# square_Rev1.net
KiCad netlist of a schematic drawn in EAGLE
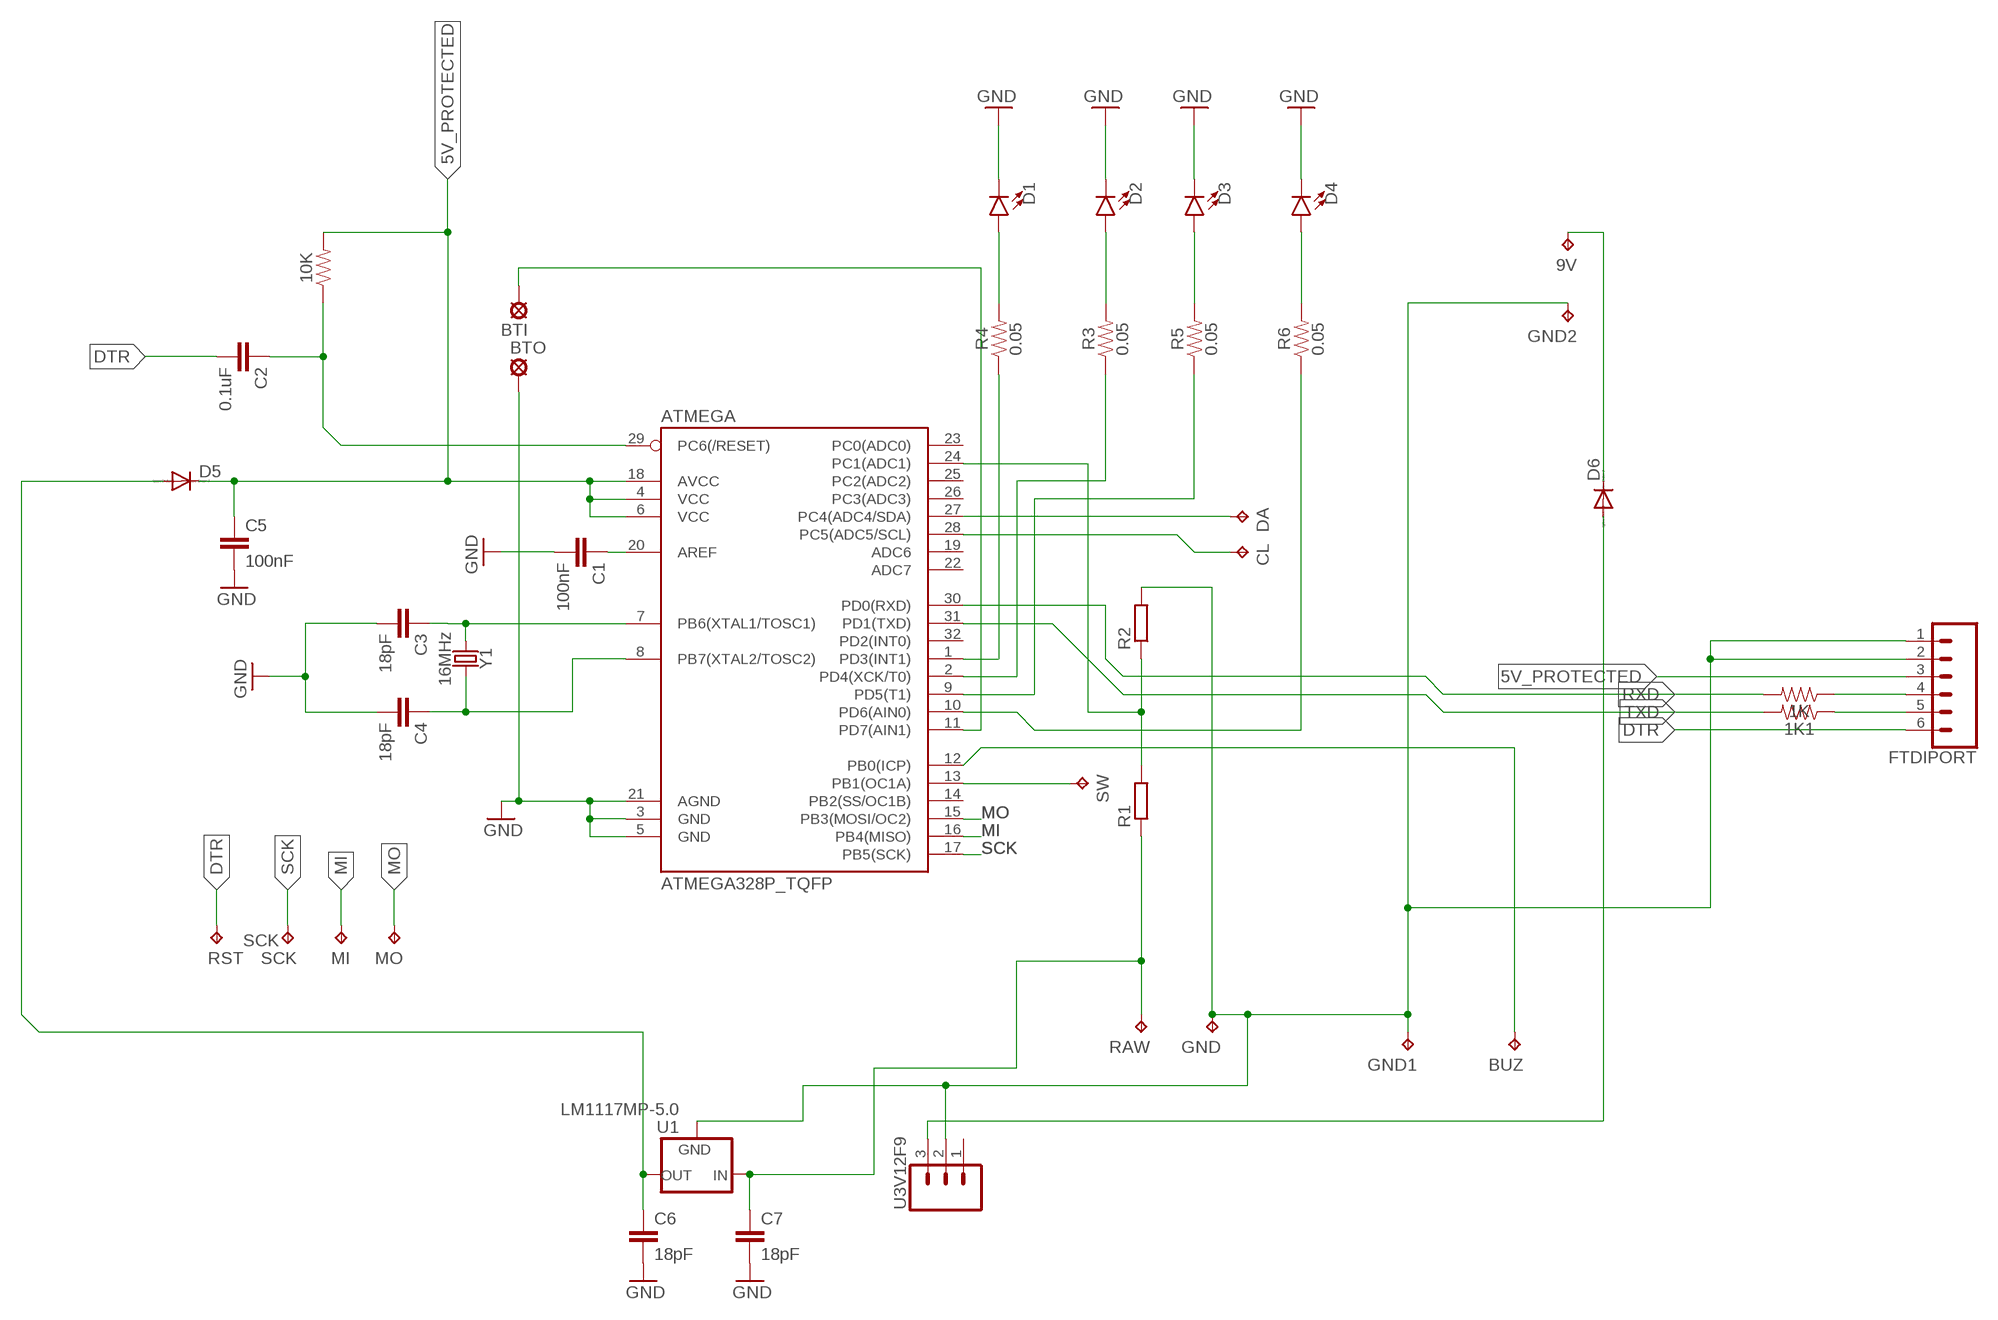
[diagram p0: schematic, sheet 1]

(export (version "E")
  (design (tool "Eeschema 10.0.6"))
  (components
    (comp (ref "1K")
      (value "0.27OHM-0603-1/10W-1%")
      (footprint "eagle-import:0603")
      (libsource (lib "eagle-import") (part "0.27OHM-0603-1/10W-1%"))
    )
    (comp (ref "1K1")
      (value "0.27OHM-0603-1/10W-1%")
      (footprint "eagle-import:0603")
      (libsource (lib "eagle-import") (part "0.27OHM-0603-1/10W-1%"))
    )
    (comp (ref "9V")
      (value "TPB2,54")
      (footprint "eagle-import:B2,54")
      (libsource (lib "eagle-import") (part "TPB2,54"))
    )
    (comp (ref "10K")
      (value "0.27OHM-0603-1/10W-1%")
      (footprint "eagle-import:0603")
      (libsource (lib "eagle-import") (part "0.27OHM-0603-1/10W-1%"))
    )
    (comp (ref "ATMEGA")
      (value "ATMEGA328P_TQFP")
      (footprint "eagle-import:TQFP32-08")
      (libsource (lib "eagle-import") (part "ATMEGA328P_TQFP"))
    )
    (comp (ref "BTI")
      (value "LSP10")
      (footprint "eagle-import:LSP10")
      (libsource (lib "eagle-import") (part "LSP10"))
    )
    (comp (ref "BTO")
      (value "LSP10")
      (footprint "eagle-import:LSP10")
      (libsource (lib "eagle-import") (part "LSP10"))
    )
    (comp (ref "BUZ")
      (value "TPB2,54")
      (footprint "eagle-import:B2,54")
      (libsource (lib "eagle-import") (part "TPB2,54"))
    )
    (comp (ref "C1")
      (value "100nF")
      (footprint "eagle-import:0603")
      (libsource (lib "eagle-import") (part "10NF-0603-50V-10%"))
    )
    (comp (ref "C2")
      (value "0.1uF")
      (footprint "eagle-import:0603")
      (libsource (lib "eagle-import") (part "10NF-0603-50V-10%"))
    )
    (comp (ref "C3")
      (value "18pF")
      (footprint "eagle-import:0603")
      (libsource (lib "eagle-import") (part "10NF-0603-50V-10%"))
    )
    (comp (ref "C4")
      (value "18pF")
      (footprint "eagle-import:0603")
      (libsource (lib "eagle-import") (part "10NF-0603-50V-10%"))
    )
    (comp (ref "C5")
      (value "100nF")
      (footprint "eagle-import:0603")
      (libsource (lib "eagle-import") (part "10NF-0603-50V-10%"))
    )
    (comp (ref "C6")
      (value "18pF")
      (footprint "eagle-import:0603")
      (libsource (lib "eagle-import") (part "10NF-0603-50V-10%"))
    )
    (comp (ref "C7")
      (value "18pF")
      (footprint "eagle-import:0603")
      (libsource (lib "eagle-import") (part "10NF-0603-50V-10%"))
    )
    (comp (ref "CL")
      (value "TPB1,27")
      (footprint "eagle-import:B1,27")
      (libsource (lib "eagle-import") (part "TPB1,27"))
    )
    (comp (ref "D1")
      (value "LED1206")
      (footprint "eagle-import:LED-1206")
      (libsource (lib "eagle-import") (part "LED1206"))
    )
    (comp (ref "D2")
      (value "LED1206")
      (footprint "eagle-import:LED-1206")
      (libsource (lib "eagle-import") (part "LED1206"))
    )
    (comp (ref "D3")
      (value "LED1206")
      (footprint "eagle-import:LED-1206")
      (libsource (lib "eagle-import") (part "LED1206"))
    )
    (comp (ref "D4")
      (value "LED1206")
      (footprint "eagle-import:LED-1206")
      (libsource (lib "eagle-import") (part "LED1206"))
    )
    (comp (ref "D5")
      (value "DIODE-SOD106A-R")
      (footprint "eagle-import:SOD106A-R")
      (libsource (lib "eagle-import") (part "DIODE-SOD106A-R"))
    )
    (comp (ref "D6")
      (value "DIODE-SOD106A-R")
      (footprint "eagle-import:SOD106A-R")
      (libsource (lib "eagle-import") (part "DIODE-SOD106A-R"))
    )
    (comp (ref "DA")
      (value "TPB1,27")
      (footprint "eagle-import:B1,27")
      (libsource (lib "eagle-import") (part "TPB1,27"))
    )
    (comp (ref "FTDIPORT")
      (value "CONN_06SMD-1MM")
      (footprint "eagle-import:1X06-1MM")
      (libsource (lib "eagle-import") (part "CONN_06SMD-1MM"))
    )
    (comp (ref "GND")
      (value "TPB2,54")
      (footprint "eagle-import:B2,54")
      (libsource (lib "eagle-import") (part "TPB2,54"))
    )
    (comp (ref "GND1")
      (value "TPB2,54")
      (footprint "eagle-import:B2,54")
      (libsource (lib "eagle-import") (part "TPB2,54"))
    )
    (comp (ref "GND2")
      (value "TPB2,54")
      (footprint "eagle-import:B2,54")
      (libsource (lib "eagle-import") (part "TPB2,54"))
    )
    (comp (ref "MI")
      (value "TPB1,27")
      (footprint "eagle-import:B1,27")
      (libsource (lib "eagle-import") (part "TPB1,27"))
    )
    (comp (ref "MO")
      (value "TPB1,27")
      (footprint "eagle-import:B1,27")
      (libsource (lib "eagle-import") (part "TPB1,27"))
    )
    (comp (ref "R1")
      (value "R-EU_R1206")
      (footprint "eagle-import:R1206")
      (libsource (lib "eagle-import") (part "R-EU_R1206"))
    )
    (comp (ref "R2")
      (value "R-EU_R1206")
      (footprint "eagle-import:R1206")
      (libsource (lib "eagle-import") (part "R-EU_R1206"))
    )
    (comp (ref "R3")
      (value "0.05")
      (footprint "eagle-import:0603")
      (libsource (lib "eagle-import") (part "0.05OHM-0603-1/5W-1%"))
    )
    (comp (ref "R4")
      (value "0.05")
      (footprint "eagle-import:0603")
      (libsource (lib "eagle-import") (part "0.05OHM-0603-1/5W-1%"))
    )
    (comp (ref "R5")
      (value "0.05")
      (footprint "eagle-import:0603")
      (libsource (lib "eagle-import") (part "0.05OHM-0603-1/5W-1%"))
    )
    (comp (ref "R6")
      (value "0.05")
      (footprint "eagle-import:0603")
      (libsource (lib "eagle-import") (part "0.05OHM-0603-1/5W-1%"))
    )
    (comp (ref "RAW")
      (value "TPB2,54")
      (footprint "eagle-import:B2,54")
      (libsource (lib "eagle-import") (part "TPB2,54"))
    )
    (comp (ref "RST")
      (value "TPB1,27")
      (footprint "eagle-import:B1,27")
      (libsource (lib "eagle-import") (part "TPB1,27"))
    )
    (comp (ref "SCK")
      (value "TPB1,27")
      (footprint "eagle-import:B1,27")
      (fields (field (name "TP_SIGNAL_NAME") "SCK"))
      (libsource (lib "eagle-import") (part "TPB1,27"))
    )
    (comp (ref "SW")
      (value "TPB1,27")
      (footprint "eagle-import:B1,27")
      (libsource (lib "eagle-import") (part "TPB1,27"))
    )
    (comp (ref "U1")
      (value "LM1117MP-5.0")
      (footprint "eagle-import:SOT223")
      (fields (field (name "MF") "Texas Instruments"))
      (libsource (lib "eagle-import") (part "LM1117?-MP5.0"))
    )
    (comp (ref "U3V12F9")
      (value "CONN_03")
      (footprint "eagle-import:1X03")
      (libsource (lib "eagle-import") (part "CONN_03"))
    )
    (comp (ref "Y1")
      (value "16MHz")
      (footprint "eagle-import:CRYSTAL-SMD-5X3.2-2PAD")
      (libsource (lib "eagle-import") (part "CRYSTALSMD-5X3.2-2PAD"))
    )
  )
  (nets
    (net (code "1") (name "5V_PROTECTED") (class "Default")
      (node (ref "10K") (pin "2") (pinfunction "2_2") (pintype "passive"))
      (node (ref "ATMEGA") (pin "18") (pinfunction "AVCC_18") (pintype "bidirectional"))
      (node (ref "ATMEGA") (pin "4") (pinfunction "VCC_4") (pintype "bidirectional"))
      (node (ref "ATMEGA") (pin "6") (pinfunction "VCC_6") (pintype "bidirectional"))
      (node (ref "C5") (pin "1") (pinfunction "1_1") (pintype "passive"))
      (node (ref "D5") (pin "C") (pinfunction "C_C") (pintype "passive"))
      (node (ref "FTDIPORT") (pin "3") (pinfunction "3_3") (pintype "passive"))
    )
    (net (code "2") (name "DTR") (class "Default")
      (node (ref "C2") (pin "2") (pinfunction "2_2") (pintype "passive"))
      (node (ref "FTDIPORT") (pin "6") (pinfunction "6_6") (pintype "passive"))
      (node (ref "RST") (pin "TP") (pinfunction "TP_TP") (pintype "input"))
    )
    (net (code "3") (name "GND") (class "Default")
      (node (ref "ATMEGA") (pin "21") (pinfunction "AGND_21") (pintype "bidirectional"))
      (node (ref "ATMEGA") (pin "3") (pinfunction "GND_3") (pintype "bidirectional"))
      (node (ref "ATMEGA") (pin "5") (pinfunction "GND_5") (pintype "bidirectional"))
      (node (ref "BTO") (pin "MP") (pinfunction "MP_MP") (pintype "passive"))
      (node (ref "C1") (pin "2") (pinfunction "2_2") (pintype "passive"))
      (node (ref "C3") (pin "2") (pinfunction "2_2") (pintype "passive"))
      (node (ref "C4") (pin "2") (pinfunction "2_2") (pintype "passive"))
      (node (ref "C5") (pin "2") (pinfunction "2_2") (pintype "passive"))
      (node (ref "C6") (pin "2") (pinfunction "2_2") (pintype "passive"))
      (node (ref "C7") (pin "2") (pinfunction "2_2") (pintype "passive"))
      (node (ref "D1") (pin "C") (pinfunction "C_C") (pintype "passive"))
      (node (ref "D2") (pin "C") (pinfunction "C_C") (pintype "passive"))
      (node (ref "D3") (pin "C") (pinfunction "C_C") (pintype "passive"))
      (node (ref "D4") (pin "C") (pinfunction "C_C") (pintype "passive"))
      (node (ref "FTDIPORT") (pin "1") (pinfunction "1_1") (pintype "passive"))
      (node (ref "FTDIPORT") (pin "2") (pinfunction "2_2") (pintype "passive"))
      (node (ref "GND") (pin "TP") (pinfunction "TP_TP") (pintype "input"))
      (node (ref "GND1") (pin "TP") (pinfunction "TP_TP") (pintype "input"))
      (node (ref "GND2") (pin "TP") (pinfunction "TP_TP") (pintype "input"))
      (node (ref "R2") (pin "2") (pinfunction "2_2") (pintype "passive"))
      (node (ref "U1") (pin "1") (pinfunction "GND_1") (pintype "input"))
      (node (ref "U3V12F9") (pin "2") (pinfunction "2_2") (pintype "passive"))
    )
    (net (code "4") (name "MI") (class "Default")
      (node (ref "ATMEGA") (pin "16") (pinfunction "PB4(MISO)_16") (pintype "bidirectional"))
      (node (ref "MI") (pin "TP") (pinfunction "TP_TP") (pintype "input"))
    )
    (net (code "5") (name "MO") (class "Default")
      (node (ref "ATMEGA") (pin "15") (pinfunction "PB3(MOSI/OC2)_15") (pintype "bidirectional"))
      (node (ref "MO") (pin "TP") (pinfunction "TP_TP") (pintype "input"))
    )
    (net (code "6") (name "Net-(1K-Pad1)") (class "Default")
      (node (ref "1K") (pin "1") (pinfunction "1_1") (pintype "passive"))
      (node (ref "FTDIPORT") (pin "4") (pinfunction "4_4") (pintype "passive"))
    )
    (net (code "7") (name "Net-(1K1-Pad1)") (class "Default")
      (node (ref "1K1") (pin "1") (pinfunction "1_1") (pintype "passive"))
      (node (ref "FTDIPORT") (pin "5") (pinfunction "5_5") (pintype "passive"))
    )
    (net (code "8") (name "Net-(9V-PadTP)") (class "Default")
      (node (ref "9V") (pin "TP") (pinfunction "TP_TP") (pintype "input"))
      (node (ref "D6") (pin "C") (pinfunction "C_C") (pintype "passive"))
    )
    (net (code "9") (name "Net-(ATMEGA-AREF)") (class "Default")
      (node (ref "ATMEGA") (pin "20") (pinfunction "AREF_20") (pintype "bidirectional"))
      (node (ref "C1") (pin "1") (pinfunction "1_1") (pintype "passive"))
    )
    (net (code "10") (name "Net-(ATMEGA-PB0(ICP))") (class "Default")
      (node (ref "ATMEGA") (pin "12") (pinfunction "PB0(ICP)_12") (pintype "bidirectional"))
      (node (ref "BUZ") (pin "TP") (pinfunction "TP_TP") (pintype "input"))
    )
    (net (code "11") (name "Net-(ATMEGA-PB1(OC1A))") (class "Default")
      (node (ref "ATMEGA") (pin "13") (pinfunction "PB1(OC1A)_13") (pintype "bidirectional"))
      (node (ref "SW") (pin "TP") (pinfunction "TP_TP") (pintype "input"))
    )
    (net (code "12") (name "Net-(ATMEGA-PB6(XTAL1{slash}TOSC1))") (class "Default")
      (node (ref "ATMEGA") (pin "7") (pinfunction "PB6(XTAL1/TOSC1)_7") (pintype "bidirectional"))
      (node (ref "C3") (pin "1") (pinfunction "1_1") (pintype "passive"))
      (node (ref "Y1") (pin "P$1") (pinfunction "1_P$1") (pintype "passive"))
    )
    (net (code "13") (name "Net-(ATMEGA-PB7(XTAL2{slash}TOSC2))") (class "Default")
      (node (ref "ATMEGA") (pin "8") (pinfunction "PB7(XTAL2/TOSC2)_8") (pintype "bidirectional"))
      (node (ref "C4") (pin "1") (pinfunction "1_1") (pintype "passive"))
      (node (ref "Y1") (pin "P$2") (pinfunction "2_P$2") (pintype "passive"))
    )
    (net (code "14") (name "Net-(ATMEGA-PC1(ADC1))") (class "Default")
      (node (ref "ATMEGA") (pin "24") (pinfunction "PC1(ADC1)_24") (pintype "bidirectional"))
      (node (ref "R1") (pin "2") (pinfunction "2_2") (pintype "passive"))
      (node (ref "R2") (pin "1") (pinfunction "1_1") (pintype "passive"))
    )
    (net (code "15") (name "Net-(ATMEGA-PC4(ADC4{slash}SDA))") (class "Default")
      (node (ref "ATMEGA") (pin "27") (pinfunction "PC4(ADC4/SDA)_27") (pintype "bidirectional"))
      (node (ref "DA") (pin "TP") (pinfunction "TP_TP") (pintype "input"))
    )
    (net (code "16") (name "Net-(ATMEGA-PC5(ADC5{slash}SCL))") (class "Default")
      (node (ref "ATMEGA") (pin "28") (pinfunction "PC5(ADC5/SCL)_28") (pintype "bidirectional"))
      (node (ref "CL") (pin "TP") (pinfunction "TP_TP") (pintype "input"))
    )
    (net (code "17") (name "Net-(ATMEGA-PC6({slash}RESET))") (class "Default")
      (node (ref "10K") (pin "1") (pinfunction "1_1") (pintype "passive"))
      (node (ref "ATMEGA") (pin "29") (pinfunction "PC6(/RESET)_29") (pintype "bidirectional"))
      (node (ref "C2") (pin "1") (pinfunction "1_1") (pintype "passive"))
    )
    (net (code "18") (name "Net-(ATMEGA-PD3(INT1))") (class "Default")
      (node (ref "ATMEGA") (pin "1") (pinfunction "PD3(INT1)_1") (pintype "bidirectional"))
      (node (ref "R4") (pin "1") (pinfunction "1_1") (pintype "passive"))
    )
    (net (code "19") (name "Net-(ATMEGA-PD4(XCK{slash}T0))") (class "Default")
      (node (ref "ATMEGA") (pin "2") (pinfunction "PD4(XCK/T0)_2") (pintype "bidirectional"))
      (node (ref "R3") (pin "1") (pinfunction "1_1") (pintype "passive"))
    )
    (net (code "20") (name "Net-(ATMEGA-PD5(T1))") (class "Default")
      (node (ref "ATMEGA") (pin "9") (pinfunction "PD5(T1)_9") (pintype "bidirectional"))
      (node (ref "R5") (pin "1") (pinfunction "1_1") (pintype "passive"))
    )
    (net (code "21") (name "Net-(ATMEGA-PD6(AIN0))") (class "Default")
      (node (ref "ATMEGA") (pin "10") (pinfunction "PD6(AIN0)_10") (pintype "bidirectional"))
      (node (ref "R6") (pin "1") (pinfunction "1_1") (pintype "passive"))
    )
    (net (code "22") (name "Net-(ATMEGA-PD7(AIN1))") (class "Default")
      (node (ref "ATMEGA") (pin "11") (pinfunction "PD7(AIN1)_11") (pintype "bidirectional"))
      (node (ref "BTI") (pin "MP") (pinfunction "MP_MP") (pintype "passive"))
    )
    (net (code "23") (name "Net-(C6-Pad1)") (class "Default")
      (node (ref "C6") (pin "1") (pinfunction "1_1") (pintype "passive"))
      (node (ref "D5") (pin "A") (pinfunction "A_A") (pintype "passive"))
      (node (ref "U1") (pin "2") (pinfunction "OUT_2") (pintype "passive"))
      (node (ref "U1") (pin "4") (pinfunction "OUT_4") (pintype "passive"))
    )
    (net (code "24") (name "Net-(D1-PadA)") (class "Default")
      (node (ref "D1") (pin "A") (pinfunction "A_A") (pintype "passive"))
      (node (ref "R4") (pin "2") (pinfunction "2_2") (pintype "passive"))
    )
    (net (code "25") (name "Net-(D2-PadA)") (class "Default")
      (node (ref "D2") (pin "A") (pinfunction "A_A") (pintype "passive"))
      (node (ref "R3") (pin "2") (pinfunction "2_2") (pintype "passive"))
    )
    (net (code "26") (name "Net-(D3-PadA)") (class "Default")
      (node (ref "D3") (pin "A") (pinfunction "A_A") (pintype "passive"))
      (node (ref "R5") (pin "2") (pinfunction "2_2") (pintype "passive"))
    )
    (net (code "27") (name "Net-(D4-PadA)") (class "Default")
      (node (ref "D4") (pin "A") (pinfunction "A_A") (pintype "passive"))
      (node (ref "R6") (pin "2") (pinfunction "2_2") (pintype "passive"))
    )
    (net (code "28") (name "Net-(D6-PadA)") (class "Default")
      (node (ref "D6") (pin "A") (pinfunction "A_A") (pintype "passive"))
      (node (ref "U3V12F9") (pin "3") (pinfunction "3_3") (pintype "passive"))
    )
    (net (code "29") (name "Net-(U1-IN)") (class "Default")
      (node (ref "C7") (pin "1") (pinfunction "1_1") (pintype "passive"))
      (node (ref "R1") (pin "1") (pinfunction "1_1") (pintype "passive"))
      (node (ref "RAW") (pin "TP") (pinfunction "TP_TP") (pintype "input"))
      (node (ref "U1") (pin "3") (pinfunction "IN_3") (pintype "input"))
    )
    (net (code "30") (name "RXD") (class "Default")
      (node (ref "1K") (pin "2") (pinfunction "2_2") (pintype "passive"))
      (node (ref "ATMEGA") (pin "30") (pinfunction "PD0(RXD)_30") (pintype "bidirectional"))
    )
    (net (code "31") (name "SCK") (class "Default")
      (node (ref "ATMEGA") (pin "17") (pinfunction "PB5(SCK)_17") (pintype "bidirectional"))
      (node (ref "SCK") (pin "TP") (pinfunction "TP_TP") (pintype "input"))
    )
    (net (code "32") (name "TXD") (class "Default")
      (node (ref "1K1") (pin "2") (pinfunction "2_2") (pintype "passive"))
      (node (ref "ATMEGA") (pin "31") (pinfunction "PD1(TXD)_31") (pintype "bidirectional"))
    )
    (net (code "33") (name "unconnected-(ATMEGA-ADC6-Pad19)") (class "Default")
      (node (ref "ATMEGA") (pin "19") (pinfunction "ADC6_19") (pintype "bidirectional"))
    )
    (net (code "34") (name "unconnected-(ATMEGA-ADC7-Pad22)") (class "Default")
      (node (ref "ATMEGA") (pin "22") (pinfunction "ADC7_22") (pintype "bidirectional"))
    )
    (net (code "35") (name "unconnected-(ATMEGA-PB2(SS{slash}OC1B)-Pad14)") (class "Default")
      (node (ref "ATMEGA") (pin "14") (pinfunction "PB2(SS/OC1B)_14") (pintype "bidirectional"))
    )
    (net (code "36") (name "unconnected-(ATMEGA-PC0(ADC0)-Pad23)") (class "Default")
      (node (ref "ATMEGA") (pin "23") (pinfunction "PC0(ADC0)_23") (pintype "bidirectional"))
    )
    (net (code "37") (name "unconnected-(ATMEGA-PC2(ADC2)-Pad25)") (class "Default")
      (node (ref "ATMEGA") (pin "25") (pinfunction "PC2(ADC2)_25") (pintype "bidirectional"))
    )
    (net (code "38") (name "unconnected-(ATMEGA-PC3(ADC3)-Pad26)") (class "Default")
      (node (ref "ATMEGA") (pin "26") (pinfunction "PC3(ADC3)_26") (pintype "bidirectional"))
    )
    (net (code "39") (name "unconnected-(ATMEGA-PD2(INT0)-Pad32)") (class "Default")
      (node (ref "ATMEGA") (pin "32") (pinfunction "PD2(INT0)_32") (pintype "bidirectional"))
    )
    (net (code "40") (name "unconnected-(U3V12F9-Pad1)") (class "Default")
      (node (ref "U3V12F9") (pin "1") (pinfunction "1_1") (pintype "passive"))
    )
  )
)
